# spicboard-v3.net
KiCad netlist of a schematic drawn in EAGLE
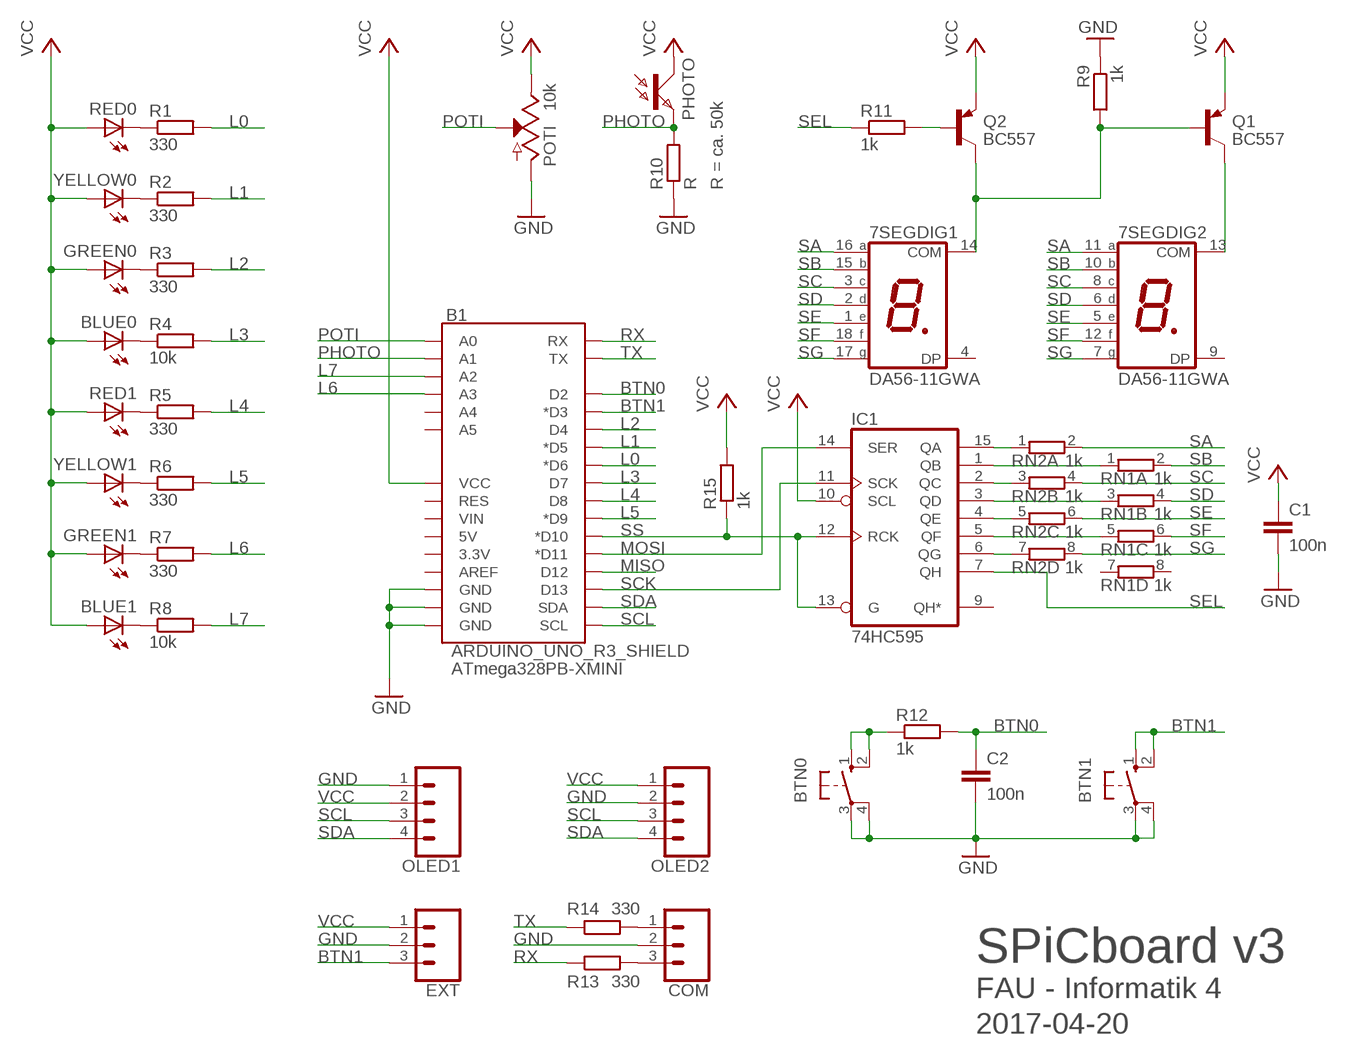
[diagram p0: schematic, sheet 1]

(export (version "E")
  (design (tool "Eeschema 10.0.6"))
  (components
    (comp (ref "7SEG")
      (value "DA56-11GWA")
      (footprint "eagle-import:DA56")
      (libsource (lib "eagle-import") (part "DA56-11GWA"))
    )
    (comp (ref "B1")
      (value "ARDUINO_UNO_R3_SHIELD")
      (footprint "eagle-import:UNO_R3_SHIELD_FINAL")
      (libsource (lib "eagle-import") (part "ARDUINO_UNO_R3_SHIELD"))
    )
    (comp (ref "BLUE0")
      (value "LED5MM")
      (footprint "eagle-import:LED5MM")
      (libsource (lib "eagle-import") (part "LED5MM"))
    )
    (comp (ref "BLUE1")
      (value "LED5MM")
      (footprint "eagle-import:LED5MM")
      (libsource (lib "eagle-import") (part "LED5MM"))
    )
    (comp (ref "BTN0")
      (value "10-XX")
      (footprint "eagle-import:B3F-10XX")
      (fields (field (name "MPN") "B3F-1000"))
      (libsource (lib "eagle-import") (part "10-XX"))
    )
    (comp (ref "BTN1")
      (value "10-XX")
      (footprint "eagle-import:B3F-10XX")
      (fields (field (name "MPN") "B3F-1000"))
      (libsource (lib "eagle-import") (part "10-XX"))
    )
    (comp (ref "C1")
      (value "100n")
      (footprint "eagle-import:C2.5-2")
      (libsource (lib "eagle-import") (part "C2.5/2"))
    )
    (comp (ref "C2")
      (value "100n")
      (footprint "eagle-import:C2.5-2")
      (libsource (lib "eagle-import") (part "C2.5/2"))
    )
    (comp (ref "COM")
      (value "CONN_03")
      (footprint "eagle-import:1X03")
      (libsource (lib "eagle-import") (part "CONN_03"))
    )
    (comp (ref "EXT")
      (value "CONN_03")
      (footprint "eagle-import:1X03")
      (libsource (lib "eagle-import") (part "CONN_03"))
    )
    (comp (ref "GREEN0")
      (value "LED5MM")
      (footprint "eagle-import:LED5MM")
      (libsource (lib "eagle-import") (part "LED5MM"))
    )
    (comp (ref "GREEN1")
      (value "LED5MM")
      (footprint "eagle-import:LED5MM")
      (libsource (lib "eagle-import") (part "LED5MM"))
    )
    (comp (ref "IC1")
      (value "74HC595")
      (footprint "eagle-import:DIL16")
      (libsource (lib "eagle-import") (part "74595NHC"))
    )
    (comp (ref "OLED1")
      (value "CONN_04")
      (footprint "eagle-import:1X04")
      (libsource (lib "eagle-import") (part "CONN_04"))
    )
    (comp (ref "OLED2")
      (value "CONN_04")
      (footprint "eagle-import:1X04")
      (libsource (lib "eagle-import") (part "CONN_04"))
    )
    (comp (ref "PHOTO")
      (value "PTPT")
      (footprint "eagle-import:PT")
      (libsource (lib "eagle-import") (part "PTPT"))
    )
    (comp (ref "POTI")
      (value "10k")
      (footprint "eagle-import:POT-PTH-ALPS")
      (libsource (lib "eagle-import") (part "POTENTIOMETER-PTH-9MM-1/20W-20%"))
    )
    (comp (ref "Q1")
      (value "BC557")
      (footprint "eagle-import:TO92-EBC")
      (libsource (lib "eagle-import") (part "BC557"))
    )
    (comp (ref "Q2")
      (value "BC557")
      (footprint "eagle-import:TO92-EBC")
      (libsource (lib "eagle-import") (part "BC557"))
    )
    (comp (ref "R1")
      (value "330")
      (footprint "eagle-import:0207_10")
      (libsource (lib "eagle-import") (part "R-EU_0207/10"))
    )
    (comp (ref "R2")
      (value "330")
      (footprint "eagle-import:0207_10")
      (libsource (lib "eagle-import") (part "R-EU_0207/10"))
    )
    (comp (ref "R3")
      (value "330")
      (footprint "eagle-import:0207_10")
      (libsource (lib "eagle-import") (part "R-EU_0207/10"))
    )
    (comp (ref "R4")
      (value "10k")
      (footprint "eagle-import:0207_10")
      (libsource (lib "eagle-import") (part "R-EU_0207/10"))
    )
    (comp (ref "R5")
      (value "330")
      (footprint "eagle-import:0207_10")
      (libsource (lib "eagle-import") (part "R-EU_0207/10"))
    )
    (comp (ref "R6")
      (value "330")
      (footprint "eagle-import:0207_10")
      (libsource (lib "eagle-import") (part "R-EU_0207/10"))
    )
    (comp (ref "R7")
      (value "330")
      (footprint "eagle-import:0207_10")
      (libsource (lib "eagle-import") (part "R-EU_0207/10"))
    )
    (comp (ref "R8")
      (value "10k")
      (footprint "eagle-import:0207_10")
      (libsource (lib "eagle-import") (part "R-EU_0207/10"))
    )
    (comp (ref "R9")
      (value "1k")
      (footprint "eagle-import:0207_10")
      (libsource (lib "eagle-import") (part "R-EU_0207/10"))
    )
    (comp (ref "R10")
      (value "R")
      (footprint "eagle-import:0207_10")
      (libsource (lib "eagle-import") (part "R-EU_0207/10"))
    )
    (comp (ref "R11")
      (value "1k")
      (footprint "eagle-import:0207_10")
      (libsource (lib "eagle-import") (part "R-EU_0207/10"))
    )
    (comp (ref "R12")
      (value "1k")
      (footprint "eagle-import:0207_10")
      (libsource (lib "eagle-import") (part "R-EU_0207/10"))
    )
    (comp (ref "R13")
      (value "330")
      (footprint "eagle-import:0207_10")
      (libsource (lib "eagle-import") (part "R-EU_0207/10"))
    )
    (comp (ref "R14")
      (value "330")
      (footprint "eagle-import:0207_10")
      (libsource (lib "eagle-import") (part "R-EU_0207/10"))
    )
    (comp (ref "R15")
      (value "1k")
      (footprint "eagle-import:0207_10")
      (libsource (lib "eagle-import") (part "R-EU_0207/10"))
    )
    (comp (ref "RED0")
      (value "LED5MM")
      (footprint "eagle-import:LED5MM")
      (libsource (lib "eagle-import") (part "LED5MM"))
    )
    (comp (ref "RED1")
      (value "LED5MM")
      (footprint "eagle-import:LED5MM")
      (libsource (lib "eagle-import") (part "LED5MM"))
    )
    (comp (ref "RN1")
      (value "1k")
      (footprint "eagle-import:SIL8")
      (libsource (lib "eagle-import") (part "E4R"))
    )
    (comp (ref "RN2")
      (value "1k")
      (footprint "eagle-import:SIL8")
      (libsource (lib "eagle-import") (part "E4R"))
    )
    (comp (ref "YELLOW0")
      (value "LED5MM")
      (footprint "eagle-import:LED5MM")
      (libsource (lib "eagle-import") (part "LED5MM"))
    )
    (comp (ref "YELLOW1")
      (value "LED5MM")
      (footprint "eagle-import:LED5MM")
      (libsource (lib "eagle-import") (part "LED5MM"))
    )
  )
  (nets
    (net (code "1") (name "/BTN0") (class "Default")
      (node (ref "B1") (pin "D2") (pinfunction "D2_D2") (pintype "bidirectional"))
      (node (ref "C2") (pin "1") (pinfunction "1_1") (pintype "passive"))
      (node (ref "R12") (pin "2") (pinfunction "2_2") (pintype "passive"))
    )
    (net (code "2") (name "/BTN1") (class "Default")
      (node (ref "B1") (pin "D3") (pinfunction "*D3_D3") (pintype "bidirectional"))
      (node (ref "BTN1") (pin "1") (pinfunction "S_1") (pintype "passive"))
      (node (ref "BTN1") (pin "2") (pinfunction "S1_2") (pintype "passive"))
      (node (ref "EXT") (pin "3") (pinfunction "3_3") (pintype "passive"))
    )
    (net (code "3") (name "/L0") (class "Default")
      (node (ref "B1") (pin "D6") (pinfunction "*D6_D6") (pintype "bidirectional"))
      (node (ref "R1") (pin "2") (pinfunction "2_2") (pintype "passive"))
    )
    (net (code "4") (name "/L1") (class "Default")
      (node (ref "B1") (pin "D5") (pinfunction "*D5_D5") (pintype "bidirectional"))
      (node (ref "R2") (pin "2") (pinfunction "2_2") (pintype "passive"))
    )
    (net (code "5") (name "/L2") (class "Default")
      (node (ref "B1") (pin "D4") (pinfunction "D4_D4") (pintype "bidirectional"))
      (node (ref "R3") (pin "2") (pinfunction "2_2") (pintype "passive"))
    )
    (net (code "6") (name "/L3") (class "Default")
      (node (ref "B1") (pin "D7") (pinfunction "D7_D7") (pintype "bidirectional"))
      (node (ref "R4") (pin "2") (pinfunction "2_2") (pintype "passive"))
    )
    (net (code "7") (name "/L4") (class "Default")
      (node (ref "B1") (pin "D8") (pinfunction "D8_D8") (pintype "bidirectional"))
      (node (ref "R5") (pin "2") (pinfunction "2_2") (pintype "passive"))
    )
    (net (code "8") (name "/L5") (class "Default")
      (node (ref "B1") (pin "D9") (pinfunction "*D9_D9") (pintype "bidirectional"))
      (node (ref "R6") (pin "2") (pinfunction "2_2") (pintype "passive"))
    )
    (net (code "9") (name "/L6") (class "Default")
      (node (ref "B1") (pin "A3") (pinfunction "A3_A3") (pintype "bidirectional"))
      (node (ref "R7") (pin "2") (pinfunction "2_2") (pintype "passive"))
    )
    (net (code "10") (name "/L7") (class "Default")
      (node (ref "B1") (pin "A2") (pinfunction "A2_A2") (pintype "bidirectional"))
      (node (ref "R8") (pin "2") (pinfunction "2_2") (pintype "passive"))
    )
    (net (code "11") (name "/MISO") (class "Default")
      (node (ref "B1") (pin "D12") (pinfunction "D12_D12") (pintype "bidirectional"))
    )
    (net (code "12") (name "/MOSI") (class "Default")
      (node (ref "B1") (pin "D11") (pinfunction "*D11_D11") (pintype "bidirectional"))
      (node (ref "IC1") (pin "14") (pinfunction "SER_14") (pintype "input"))
    )
    (net (code "13") (name "/PHOTO") (class "Default")
      (node (ref "B1") (pin "A1") (pinfunction "A1_A1") (pintype "bidirectional"))
      (node (ref "PHOTO") (pin "E") (pinfunction "E_E") (pintype "passive"))
      (node (ref "R10") (pin "2") (pinfunction "2_2") (pintype "passive"))
    )
    (net (code "14") (name "/POTI") (class "Default")
      (node (ref "B1") (pin "A0") (pinfunction "A0_A0") (pintype "bidirectional"))
      (node (ref "POTI") (pin "P$2") (pinfunction "S_P$2") (pintype "passive"))
    )
    (net (code "15") (name "/RX") (class "Default")
      (node (ref "B1") (pin "RX") (pinfunction "RX_RX") (pintype "bidirectional"))
      (node (ref "R13") (pin "1") (pinfunction "1_1") (pintype "passive"))
    )
    (net (code "16") (name "/SA") (class "Default")
      (node (ref "7SEG") (pin "11") (pinfunction "A_11") (pintype "passive"))
      (node (ref "7SEG") (pin "16") (pinfunction "A_16") (pintype "passive"))
      (node (ref "RN2") (pin "2") (pinfunction "2_2") (pintype "passive"))
    )
    (net (code "17") (name "/SB") (class "Default")
      (node (ref "7SEG") (pin "10") (pinfunction "B_10") (pintype "passive"))
      (node (ref "7SEG") (pin "15") (pinfunction "B_15") (pintype "passive"))
      (node (ref "RN1") (pin "2") (pinfunction "2_2") (pintype "passive"))
    )
    (net (code "18") (name "/SC") (class "Default")
      (node (ref "7SEG") (pin "3") (pinfunction "C_3") (pintype "passive"))
      (node (ref "7SEG") (pin "8") (pinfunction "C_8") (pintype "passive"))
      (node (ref "RN2") (pin "4") (pinfunction "2_4") (pintype "passive"))
    )
    (net (code "19") (name "/SCK") (class "Default")
      (node (ref "B1") (pin "D13") (pinfunction "D13_D13") (pintype "bidirectional"))
      (node (ref "IC1") (pin "11") (pinfunction "SCK_11") (pintype "input"))
    )
    (net (code "20") (name "/SCL") (class "Default")
      (node (ref "B1") (pin "SCL") (pinfunction "SCL_SCL") (pintype "bidirectional"))
      (node (ref "OLED1") (pin "3") (pinfunction "3_3") (pintype "passive"))
      (node (ref "OLED2") (pin "3") (pinfunction "3_3") (pintype "passive"))
    )
    (net (code "21") (name "/SD") (class "Default")
      (node (ref "7SEG") (pin "2") (pinfunction "D_2") (pintype "passive"))
      (node (ref "7SEG") (pin "6") (pinfunction "D_6") (pintype "passive"))
      (node (ref "RN1") (pin "4") (pinfunction "2_4") (pintype "passive"))
    )
    (net (code "22") (name "/SDA") (class "Default")
      (node (ref "B1") (pin "SDA") (pinfunction "SDA_SDA") (pintype "bidirectional"))
      (node (ref "OLED1") (pin "4") (pinfunction "4_4") (pintype "passive"))
      (node (ref "OLED2") (pin "4") (pinfunction "4_4") (pintype "passive"))
    )
    (net (code "23") (name "/SE") (class "Default")
      (node (ref "7SEG") (pin "1") (pinfunction "E_1") (pintype "passive"))
      (node (ref "7SEG") (pin "5") (pinfunction "E_5") (pintype "passive"))
      (node (ref "RN2") (pin "6") (pinfunction "2_6") (pintype "passive"))
    )
    (net (code "24") (name "/SEL") (class "Default")
      (node (ref "IC1") (pin "7") (pinfunction "QH_7") (pintype "tri_state"))
      (node (ref "R11") (pin "1") (pinfunction "1_1") (pintype "passive"))
    )
    (net (code "25") (name "/SF") (class "Default")
      (node (ref "7SEG") (pin "12") (pinfunction "F_12") (pintype "passive"))
      (node (ref "7SEG") (pin "18") (pinfunction "F_18") (pintype "passive"))
      (node (ref "RN1") (pin "6") (pinfunction "2_6") (pintype "passive"))
    )
    (net (code "26") (name "/SG") (class "Default")
      (node (ref "7SEG") (pin "17") (pinfunction "G_17") (pintype "passive"))
      (node (ref "7SEG") (pin "7") (pinfunction "G_7") (pintype "passive"))
      (node (ref "RN2") (pin "8") (pinfunction "2_8") (pintype "passive"))
    )
    (net (code "27") (name "/SS") (class "Default")
      (node (ref "B1") (pin "D10") (pinfunction "*D10_D10") (pintype "bidirectional"))
      (node (ref "IC1") (pin "12") (pinfunction "RCK_12") (pintype "input"))
      (node (ref "IC1") (pin "13") (pinfunction "G_13") (pintype "input"))
      (node (ref "R15") (pin "1") (pinfunction "1_1") (pintype "passive"))
    )
    (net (code "28") (name "/TX") (class "Default")
      (node (ref "B1") (pin "TX") (pinfunction "TX_TX") (pintype "bidirectional"))
      (node (ref "R14") (pin "1") (pinfunction "1_1") (pintype "passive"))
    )
    (net (code "29") (name "GND") (class "Default")
      (node (ref "B1") (pin "GND@0") (pinfunction "GND_GND@0") (pintype "bidirectional"))
      (node (ref "B1") (pin "GND@1") (pinfunction "GND_GND@1") (pintype "bidirectional"))
      (node (ref "B1") (pin "GND@2") (pinfunction "GND_GND@2") (pintype "bidirectional"))
      (node (ref "BTN0") (pin "3") (pinfunction "P_3") (pintype "passive"))
      (node (ref "BTN0") (pin "4") (pinfunction "P1_4") (pintype "passive"))
      (node (ref "BTN1") (pin "3") (pinfunction "P_3") (pintype "passive"))
      (node (ref "BTN1") (pin "4") (pinfunction "P1_4") (pintype "passive"))
      (node (ref "C1") (pin "2") (pinfunction "2_2") (pintype "passive"))
      (node (ref "C2") (pin "2") (pinfunction "2_2") (pintype "passive"))
      (node (ref "COM") (pin "2") (pinfunction "2_2") (pintype "passive"))
      (node (ref "EXT") (pin "2") (pinfunction "2_2") (pintype "passive"))
      (node (ref "OLED1") (pin "1") (pinfunction "1_1") (pintype "passive"))
      (node (ref "OLED2") (pin "2") (pinfunction "2_2") (pintype "passive"))
      (node (ref "POTI") (pin "P$3") (pinfunction "A_P$3") (pintype "passive"))
      (node (ref "R10") (pin "1") (pinfunction "1_1") (pintype "passive"))
      (node (ref "R9") (pin "1") (pinfunction "1_1") (pintype "passive"))
    )
    (net (code "30") (name "Net-(7SEGA-COM)") (class "Default")
      (node (ref "7SEG") (pin "14") (pinfunction "COM_14") (pintype "passive"))
      (node (ref "Q1") (pin "B") (pinfunction "B_B") (pintype "passive"))
      (node (ref "Q2") (pin "C") (pinfunction "C_C") (pintype "passive"))
      (node (ref "R9") (pin "2") (pinfunction "2_2") (pintype "passive"))
    )
    (net (code "31") (name "Net-(7SEGB-COM)") (class "Default")
      (node (ref "7SEG") (pin "13") (pinfunction "COM_13") (pintype "passive"))
      (node (ref "Q1") (pin "C") (pinfunction "C_C") (pintype "passive"))
    )
    (net (code "32") (name "Net-(BLUE0-C)") (class "Default")
      (node (ref "BLUE0") (pin "K") (pinfunction "C_K") (pintype "passive"))
      (node (ref "R4") (pin "1") (pinfunction "1_1") (pintype "passive"))
    )
    (net (code "33") (name "Net-(BLUE1-C)") (class "Default")
      (node (ref "BLUE1") (pin "K") (pinfunction "C_K") (pintype "passive"))
      (node (ref "R8") (pin "1") (pinfunction "1_1") (pintype "passive"))
    )
    (net (code "34") (name "Net-(BTN0-S)") (class "Default")
      (node (ref "BTN0") (pin "1") (pinfunction "S_1") (pintype "passive"))
      (node (ref "BTN0") (pin "2") (pinfunction "S1_2") (pintype "passive"))
      (node (ref "R12") (pin "1") (pinfunction "1_1") (pintype "passive"))
    )
    (net (code "35") (name "Net-(COM-Pad1)") (class "Default")
      (node (ref "COM") (pin "1") (pinfunction "1_1") (pintype "passive"))
      (node (ref "R14") (pin "2") (pinfunction "2_2") (pintype "passive"))
    )
    (net (code "36") (name "Net-(COM-Pad3)") (class "Default")
      (node (ref "COM") (pin "3") (pinfunction "3_3") (pintype "passive"))
      (node (ref "R13") (pin "2") (pinfunction "2_2") (pintype "passive"))
    )
    (net (code "37") (name "Net-(GREEN0-C)") (class "Default")
      (node (ref "GREEN0") (pin "K") (pinfunction "C_K") (pintype "passive"))
      (node (ref "R3") (pin "1") (pinfunction "1_1") (pintype "passive"))
    )
    (net (code "38") (name "Net-(GREEN1-C)") (class "Default")
      (node (ref "GREEN1") (pin "K") (pinfunction "C_K") (pintype "passive"))
      (node (ref "R7") (pin "1") (pinfunction "1_1") (pintype "passive"))
    )
    (net (code "39") (name "Net-(IC1A-QA)") (class "Default")
      (node (ref "IC1") (pin "15") (pinfunction "QA_15") (pintype "tri_state"))
      (node (ref "RN2") (pin "1") (pinfunction "1_1") (pintype "passive"))
    )
    (net (code "40") (name "Net-(IC1A-QB)") (class "Default")
      (node (ref "IC1") (pin "1") (pinfunction "QB_1") (pintype "tri_state"))
      (node (ref "RN1") (pin "1") (pinfunction "1_1") (pintype "passive"))
    )
    (net (code "41") (name "Net-(IC1A-QC)") (class "Default")
      (node (ref "IC1") (pin "2") (pinfunction "QC_2") (pintype "tri_state"))
      (node (ref "RN2") (pin "3") (pinfunction "1_3") (pintype "passive"))
    )
    (net (code "42") (name "Net-(IC1A-QD)") (class "Default")
      (node (ref "IC1") (pin "3") (pinfunction "QD_3") (pintype "tri_state"))
      (node (ref "RN1") (pin "3") (pinfunction "1_3") (pintype "passive"))
    )
    (net (code "43") (name "Net-(IC1A-QE)") (class "Default")
      (node (ref "IC1") (pin "4") (pinfunction "QE_4") (pintype "tri_state"))
      (node (ref "RN2") (pin "5") (pinfunction "1_5") (pintype "passive"))
    )
    (net (code "44") (name "Net-(IC1A-QF)") (class "Default")
      (node (ref "IC1") (pin "5") (pinfunction "QF_5") (pintype "tri_state"))
      (node (ref "RN1") (pin "5") (pinfunction "1_5") (pintype "passive"))
    )
    (net (code "45") (name "Net-(IC1A-QG)") (class "Default")
      (node (ref "IC1") (pin "6") (pinfunction "QG_6") (pintype "tri_state"))
      (node (ref "RN2") (pin "7") (pinfunction "1_7") (pintype "passive"))
    )
    (net (code "46") (name "Net-(Q2-PadB)") (class "Default")
      (node (ref "Q2") (pin "B") (pinfunction "B_B") (pintype "passive"))
      (node (ref "R11") (pin "2") (pinfunction "2_2") (pintype "passive"))
    )
    (net (code "47") (name "Net-(RED0-C)") (class "Default")
      (node (ref "R1") (pin "1") (pinfunction "1_1") (pintype "passive"))
      (node (ref "RED0") (pin "K") (pinfunction "C_K") (pintype "passive"))
    )
    (net (code "48") (name "Net-(RED1-C)") (class "Default")
      (node (ref "R5") (pin "1") (pinfunction "1_1") (pintype "passive"))
      (node (ref "RED1") (pin "K") (pinfunction "C_K") (pintype "passive"))
    )
    (net (code "49") (name "Net-(YELLOW0-C)") (class "Default")
      (node (ref "R2") (pin "1") (pinfunction "1_1") (pintype "passive"))
      (node (ref "YELLOW0") (pin "K") (pinfunction "C_K") (pintype "passive"))
    )
    (net (code "50") (name "Net-(YELLOW1-C)") (class "Default")
      (node (ref "R6") (pin "1") (pinfunction "1_1") (pintype "passive"))
      (node (ref "YELLOW1") (pin "K") (pinfunction "C_K") (pintype "passive"))
    )
    (net (code "51") (name "VCC") (class "Default")
      (node (ref "B1") (pin "VCC") (pinfunction "VCC_VCC") (pintype "bidirectional"))
      (node (ref "BLUE0") (pin "A") (pinfunction "A_A") (pintype "passive"))
      (node (ref "BLUE1") (pin "A") (pinfunction "A_A") (pintype "passive"))
      (node (ref "C1") (pin "1") (pinfunction "1_1") (pintype "passive"))
      (node (ref "EXT") (pin "1") (pinfunction "1_1") (pintype "passive"))
      (node (ref "GREEN0") (pin "A") (pinfunction "A_A") (pintype "passive"))
      (node (ref "GREEN1") (pin "A") (pinfunction "A_A") (pintype "passive"))
      (node (ref "IC1") (pin "10") (pinfunction "SCL_10") (pintype "input"))
      (node (ref "OLED1") (pin "2") (pinfunction "2_2") (pintype "passive"))
      (node (ref "OLED2") (pin "1") (pinfunction "1_1") (pintype "passive"))
      (node (ref "PHOTO") (pin "C") (pinfunction "C_C") (pintype "passive"))
      (node (ref "POTI") (pin "P$1") (pinfunction "E_P$1") (pintype "passive"))
      (node (ref "Q1") (pin "E") (pinfunction "E_E") (pintype "passive"))
      (node (ref "Q2") (pin "E") (pinfunction "E_E") (pintype "passive"))
      (node (ref "R15") (pin "2") (pinfunction "2_2") (pintype "passive"))
      (node (ref "RED0") (pin "A") (pinfunction "A_A") (pintype "passive"))
      (node (ref "RED1") (pin "A") (pinfunction "A_A") (pintype "passive"))
      (node (ref "YELLOW0") (pin "A") (pinfunction "A_A") (pintype "passive"))
      (node (ref "YELLOW1") (pin "A") (pinfunction "A_A") (pintype "passive"))
    )
    (net (code "52") (name "unconnected-(7SEGA-DP-Pad4)") (class "Default")
      (node (ref "7SEG") (pin "4") (pinfunction "DP_4") (pintype "passive"))
    )
    (net (code "53") (name "unconnected-(7SEGB-DP-Pad9)") (class "Default")
      (node (ref "7SEG") (pin "9") (pinfunction "DP_9") (pintype "passive"))
    )
    (net (code "54") (name "unconnected-(B1-Pad3.3V)") (class "Default")
      (node (ref "B1") (pin "3.3V") (pinfunction "3.3V_3.3V") (pintype "bidirectional"))
    )
    (net (code "55") (name "unconnected-(B1-Pad5V)") (class "Default")
      (node (ref "B1") (pin "5V") (pinfunction "5V_5V") (pintype "bidirectional"))
    )
    (net (code "56") (name "unconnected-(B1-PadA4)") (class "Default")
      (node (ref "B1") (pin "A4") (pinfunction "A4_A4") (pintype "bidirectional"))
    )
    (net (code "57") (name "unconnected-(B1-PadA5)") (class "Default")
      (node (ref "B1") (pin "A5") (pinfunction "A5_A5") (pintype "bidirectional"))
    )
    (net (code "58") (name "unconnected-(B1-PadAREF)") (class "Default")
      (node (ref "B1") (pin "AREF") (pinfunction "AREF_AREF") (pintype "bidirectional"))
    )
    (net (code "59") (name "unconnected-(B1-PadRES)") (class "Default")
      (node (ref "B1") (pin "RES") (pinfunction "RES_RES") (pintype "bidirectional"))
    )
    (net (code "60") (name "unconnected-(B1-PadVIN)") (class "Default")
      (node (ref "B1") (pin "VIN") (pinfunction "VIN_VIN") (pintype "bidirectional"))
    )
    (net (code "61") (name "unconnected-(IC1A-QH*-Pad9)") (class "Default")
      (node (ref "IC1") (pin "9") (pinfunction "QH*_9") (pintype "tri_state"))
    )
    (net (code "62") (name "unconnected-(RN1D-1-Pad7)") (class "Default")
      (node (ref "RN1") (pin "7") (pinfunction "1_7") (pintype "passive"))
    )
    (net (code "63") (name "unconnected-(RN1D-2-Pad8)") (class "Default")
      (node (ref "RN1") (pin "8") (pinfunction "2_8") (pintype "passive"))
    )
  )
)
